# TriacFanout.net
KiCad netlist of a schematic drawn in EAGLE
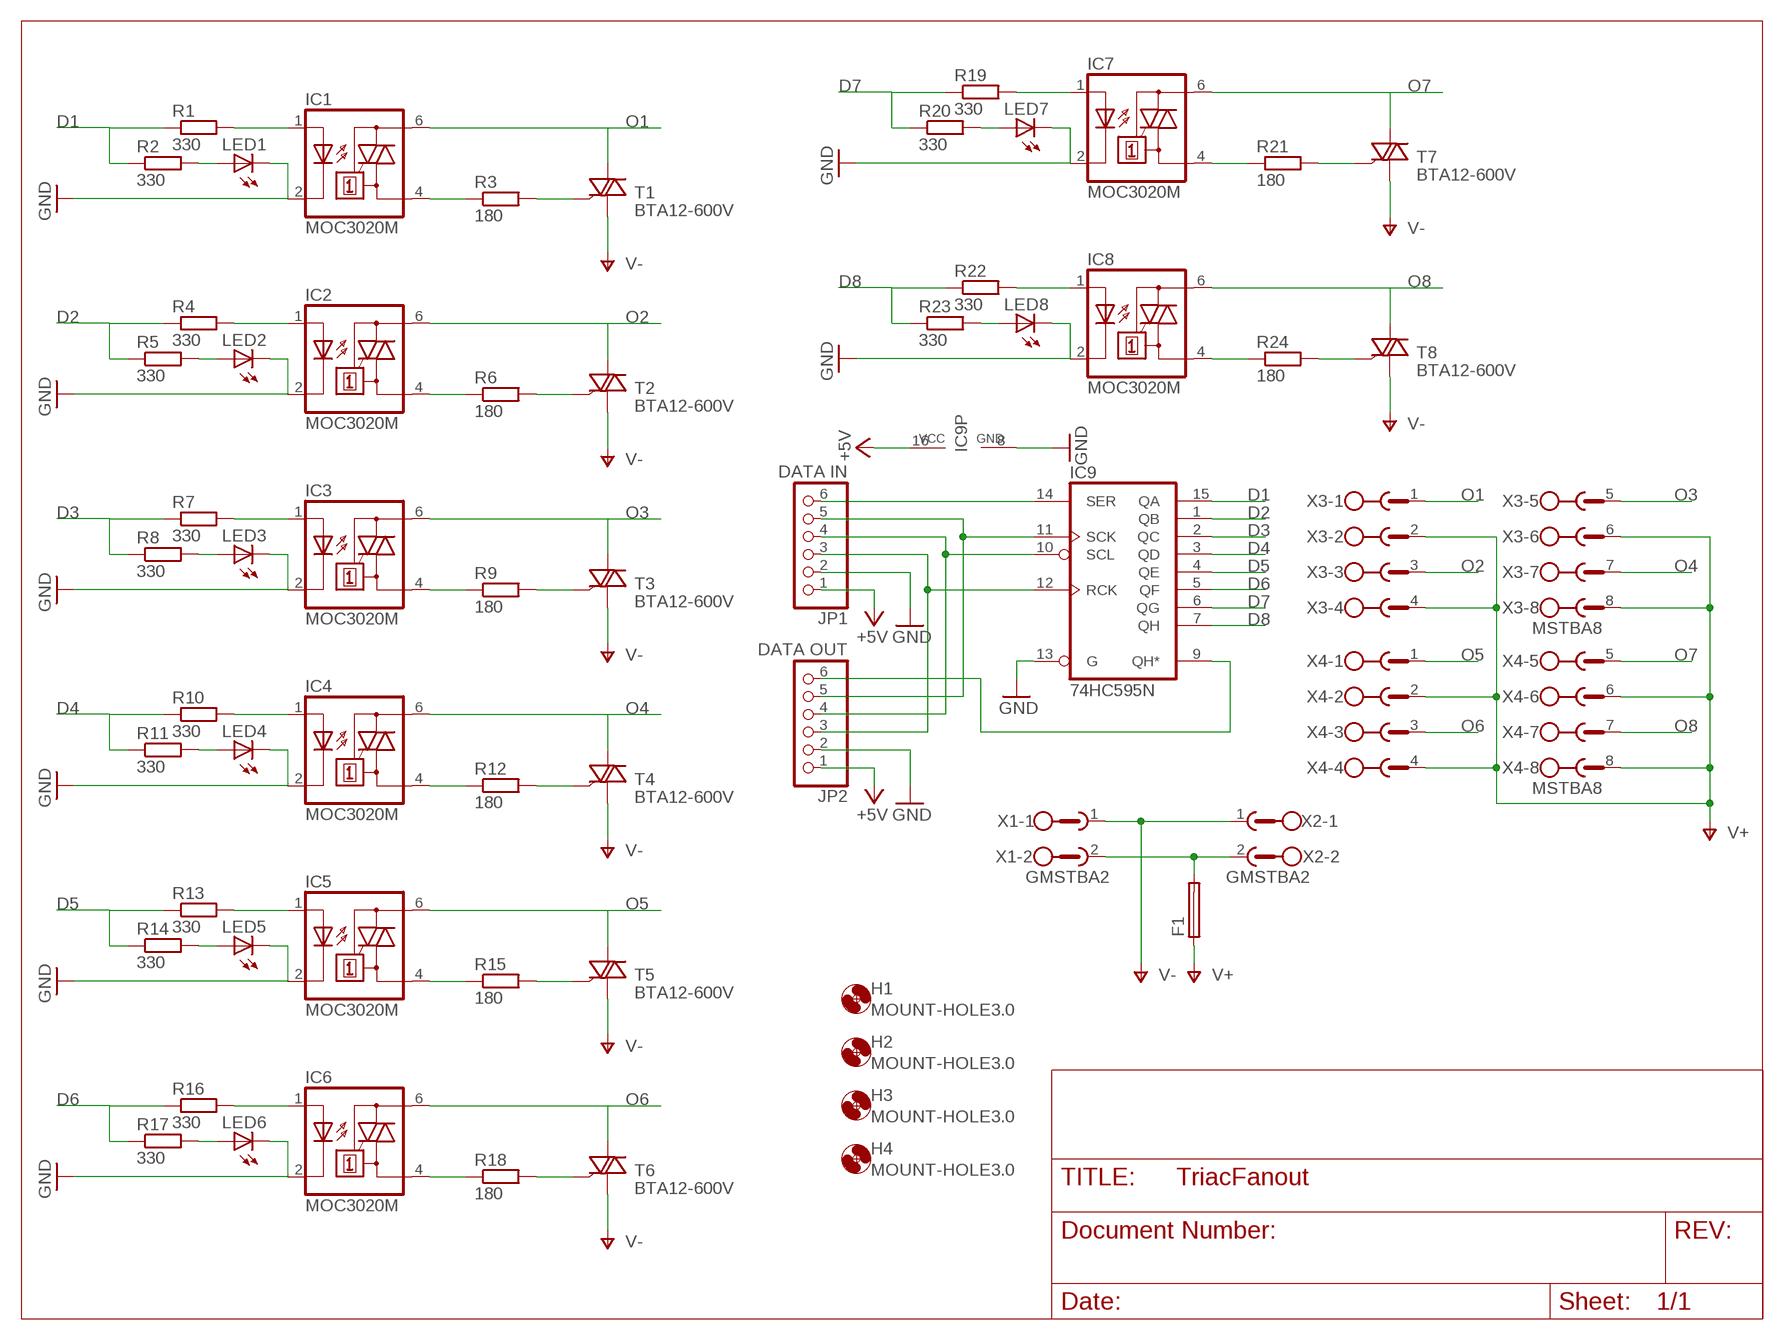
[diagram p0: schematic, sheet 1]

(export (version "E")
  (design (tool "Eeschema 10.0.6"))
  (components
    (comp (ref "F1")
      (value "SH22,5")
      (footprint "eagle-import:SH22,5")
      (fields (field (name "MF") "SCHURTER") (field (name "MPN") "0031.8201"))
      (libsource (lib "eagle-import") (part "SH22,5"))
    )
    (comp (ref "H1")
      (value "MOUNT-HOLE3.0")
      (footprint "eagle-import:3,0")
      (libsource (lib "eagle-import") (part "MOUNT-HOLE3.0"))
    )
    (comp (ref "H2")
      (value "MOUNT-HOLE3.0")
      (footprint "eagle-import:3,0")
      (libsource (lib "eagle-import") (part "MOUNT-HOLE3.0"))
    )
    (comp (ref "H3")
      (value "MOUNT-HOLE3.0")
      (footprint "eagle-import:3,0")
      (libsource (lib "eagle-import") (part "MOUNT-HOLE3.0"))
    )
    (comp (ref "H4")
      (value "MOUNT-HOLE3.0")
      (footprint "eagle-import:3,0")
      (libsource (lib "eagle-import") (part "MOUNT-HOLE3.0"))
    )
    (comp (ref "IC1")
      (value "MOC3020M")
      (footprint "eagle-import:DIL06")
      (fields (field (name "MF") "FAIRCHILD SEMICONDUCTOR") (field (name "MPN") "MOC3020-M"))
      (libsource (lib "eagle-import") (part "MOC30M20"))
    )
    (comp (ref "IC2")
      (value "MOC3020M")
      (footprint "eagle-import:DIL06")
      (fields (field (name "MF") "FAIRCHILD SEMICONDUCTOR") (field (name "MPN") "MOC3020-M"))
      (libsource (lib "eagle-import") (part "MOC30M20"))
    )
    (comp (ref "IC3")
      (value "MOC3020M")
      (footprint "eagle-import:DIL06")
      (fields (field (name "MF") "FAIRCHILD SEMICONDUCTOR") (field (name "MPN") "MOC3020-M"))
      (libsource (lib "eagle-import") (part "MOC30M20"))
    )
    (comp (ref "IC4")
      (value "MOC3020M")
      (footprint "eagle-import:DIL06")
      (fields (field (name "MF") "FAIRCHILD SEMICONDUCTOR") (field (name "MPN") "MOC3020-M"))
      (libsource (lib "eagle-import") (part "MOC30M20"))
    )
    (comp (ref "IC5")
      (value "MOC3020M")
      (footprint "eagle-import:DIL06")
      (fields (field (name "MF") "FAIRCHILD SEMICONDUCTOR") (field (name "MPN") "MOC3020-M"))
      (libsource (lib "eagle-import") (part "MOC30M20"))
    )
    (comp (ref "IC6")
      (value "MOC3020M")
      (footprint "eagle-import:DIL06")
      (fields (field (name "MF") "FAIRCHILD SEMICONDUCTOR") (field (name "MPN") "MOC3020-M"))
      (libsource (lib "eagle-import") (part "MOC30M20"))
    )
    (comp (ref "IC7")
      (value "MOC3020M")
      (footprint "eagle-import:DIL06")
      (fields (field (name "MF") "FAIRCHILD SEMICONDUCTOR") (field (name "MPN") "MOC3020-M"))
      (libsource (lib "eagle-import") (part "MOC30M20"))
    )
    (comp (ref "IC8")
      (value "MOC3020M")
      (footprint "eagle-import:DIL06")
      (fields (field (name "MF") "FAIRCHILD SEMICONDUCTOR") (field (name "MPN") "MOC3020-M"))
      (libsource (lib "eagle-import") (part "MOC30M20"))
    )
    (comp (ref "IC9")
      (value "74HC595N")
      (footprint "eagle-import:DIL16")
      (libsource (lib "eagle-import") (part "74595NHC"))
    )
    (comp (ref "JP1")
      (value "DATA IN")
      (footprint "eagle-import:1X06")
      (libsource (lib "eagle-import") (part "PINHD-1X6"))
    )
    (comp (ref "JP2")
      (value "DATA OUT")
      (footprint "eagle-import:1X06")
      (libsource (lib "eagle-import") (part "PINHD-1X6"))
    )
    (comp (ref "LED1")
      (value "LED5MM")
      (footprint "eagle-import:LED5MM")
      (libsource (lib "eagle-import") (part "LED5MM"))
    )
    (comp (ref "LED2")
      (value "LED5MM")
      (footprint "eagle-import:LED5MM")
      (libsource (lib "eagle-import") (part "LED5MM"))
    )
    (comp (ref "LED3")
      (value "LED5MM")
      (footprint "eagle-import:LED5MM")
      (libsource (lib "eagle-import") (part "LED5MM"))
    )
    (comp (ref "LED4")
      (value "LED5MM")
      (footprint "eagle-import:LED5MM")
      (libsource (lib "eagle-import") (part "LED5MM"))
    )
    (comp (ref "LED5")
      (value "LED5MM")
      (footprint "eagle-import:LED5MM")
      (libsource (lib "eagle-import") (part "LED5MM"))
    )
    (comp (ref "LED6")
      (value "LED5MM")
      (footprint "eagle-import:LED5MM")
      (libsource (lib "eagle-import") (part "LED5MM"))
    )
    (comp (ref "LED7")
      (value "LED5MM")
      (footprint "eagle-import:LED5MM")
      (libsource (lib "eagle-import") (part "LED5MM"))
    )
    (comp (ref "LED8")
      (value "LED5MM")
      (footprint "eagle-import:LED5MM")
      (libsource (lib "eagle-import") (part "LED5MM"))
    )
    (comp (ref "R1")
      (value "330")
      (footprint "eagle-import:0204_7")
      (libsource (lib "eagle-import") (part "R-EU_0204/7"))
    )
    (comp (ref "R2")
      (value "330")
      (footprint "eagle-import:0204_7")
      (libsource (lib "eagle-import") (part "R-EU_0204/7"))
    )
    (comp (ref "R3")
      (value "180")
      (footprint "eagle-import:0204_7")
      (libsource (lib "eagle-import") (part "R-EU_0204/7"))
    )
    (comp (ref "R4")
      (value "330")
      (footprint "eagle-import:0204_7")
      (libsource (lib "eagle-import") (part "R-EU_0204/7"))
    )
    (comp (ref "R5")
      (value "330")
      (footprint "eagle-import:0204_7")
      (libsource (lib "eagle-import") (part "R-EU_0204/7"))
    )
    (comp (ref "R6")
      (value "180")
      (footprint "eagle-import:0204_7")
      (libsource (lib "eagle-import") (part "R-EU_0204/7"))
    )
    (comp (ref "R7")
      (value "330")
      (footprint "eagle-import:0204_7")
      (libsource (lib "eagle-import") (part "R-EU_0204/7"))
    )
    (comp (ref "R8")
      (value "330")
      (footprint "eagle-import:0204_7")
      (libsource (lib "eagle-import") (part "R-EU_0204/7"))
    )
    (comp (ref "R9")
      (value "180")
      (footprint "eagle-import:0204_7")
      (libsource (lib "eagle-import") (part "R-EU_0204/7"))
    )
    (comp (ref "R10")
      (value "330")
      (footprint "eagle-import:0204_7")
      (libsource (lib "eagle-import") (part "R-EU_0204/7"))
    )
    (comp (ref "R11")
      (value "330")
      (footprint "eagle-import:0204_7")
      (libsource (lib "eagle-import") (part "R-EU_0204/7"))
    )
    (comp (ref "R12")
      (value "180")
      (footprint "eagle-import:0204_7")
      (libsource (lib "eagle-import") (part "R-EU_0204/7"))
    )
    (comp (ref "R13")
      (value "330")
      (footprint "eagle-import:0204_7")
      (libsource (lib "eagle-import") (part "R-EU_0204/7"))
    )
    (comp (ref "R14")
      (value "330")
      (footprint "eagle-import:0204_7")
      (libsource (lib "eagle-import") (part "R-EU_0204/7"))
    )
    (comp (ref "R15")
      (value "180")
      (footprint "eagle-import:0204_7")
      (libsource (lib "eagle-import") (part "R-EU_0204/7"))
    )
    (comp (ref "R16")
      (value "330")
      (footprint "eagle-import:0204_7")
      (libsource (lib "eagle-import") (part "R-EU_0204/7"))
    )
    (comp (ref "R17")
      (value "330")
      (footprint "eagle-import:0204_7")
      (libsource (lib "eagle-import") (part "R-EU_0204/7"))
    )
    (comp (ref "R18")
      (value "180")
      (footprint "eagle-import:0204_7")
      (libsource (lib "eagle-import") (part "R-EU_0204/7"))
    )
    (comp (ref "R19")
      (value "330")
      (footprint "eagle-import:0204_7")
      (libsource (lib "eagle-import") (part "R-EU_0204/7"))
    )
    (comp (ref "R20")
      (value "330")
      (footprint "eagle-import:0204_7")
      (libsource (lib "eagle-import") (part "R-EU_0204/7"))
    )
    (comp (ref "R21")
      (value "180")
      (footprint "eagle-import:0204_7")
      (libsource (lib "eagle-import") (part "R-EU_0204/7"))
    )
    (comp (ref "R22")
      (value "330")
      (footprint "eagle-import:0204_7")
      (libsource (lib "eagle-import") (part "R-EU_0204/7"))
    )
    (comp (ref "R23")
      (value "330")
      (footprint "eagle-import:0204_7")
      (libsource (lib "eagle-import") (part "R-EU_0204/7"))
    )
    (comp (ref "R24")
      (value "180")
      (footprint "eagle-import:0204_7")
      (libsource (lib "eagle-import") (part "R-EU_0204/7"))
    )
    (comp (ref "T1")
      (value "BTA12-600V")
      (footprint "eagle-import:TO220V")
      (libsource (lib "eagle-import") (part "BTA12-600V"))
    )
    (comp (ref "T2")
      (value "BTA12-600V")
      (footprint "eagle-import:TO220V")
      (libsource (lib "eagle-import") (part "BTA12-600V"))
    )
    (comp (ref "T3")
      (value "BTA12-600V")
      (footprint "eagle-import:TO220V")
      (libsource (lib "eagle-import") (part "BTA12-600V"))
    )
    (comp (ref "T4")
      (value "BTA12-600V")
      (footprint "eagle-import:TO220V")
      (libsource (lib "eagle-import") (part "BTA12-600V"))
    )
    (comp (ref "T5")
      (value "BTA12-600V")
      (footprint "eagle-import:TO220V")
      (libsource (lib "eagle-import") (part "BTA12-600V"))
    )
    (comp (ref "T6")
      (value "BTA12-600V")
      (footprint "eagle-import:TO220V")
      (libsource (lib "eagle-import") (part "BTA12-600V"))
    )
    (comp (ref "T7")
      (value "BTA12-600V")
      (footprint "eagle-import:TO220V")
      (libsource (lib "eagle-import") (part "BTA12-600V"))
    )
    (comp (ref "T8")
      (value "BTA12-600V")
      (footprint "eagle-import:TO220V")
      (libsource (lib "eagle-import") (part "BTA12-600V"))
    )
    (comp (ref "X1")
      (value "GMSTBA2")
      (footprint "eagle-import:GMSTBA2")
      (fields (field (name "MF") "FARNELL") (field (name "MPN") "1757242"))
      (libsource (lib "eagle-import") (part "GMSTBA2"))
    )
    (comp (ref "X2")
      (value "GMSTBA2")
      (footprint "eagle-import:GMSTBA2")
      (fields (field (name "MF") "FARNELL") (field (name "MPN") "1757242"))
      (libsource (lib "eagle-import") (part "GMSTBA2"))
    )
    (comp (ref "X3")
      (value "MSTBA8")
      (footprint "eagle-import:MSTBA8")
      (fields (field (name "MF") "FARNELL") (field (name "MPN") "1757307"))
      (libsource (lib "eagle-import") (part "MSTBA8"))
    )
    (comp (ref "X4")
      (value "MSTBA8")
      (footprint "eagle-import:MSTBA8")
      (fields (field (name "MF") "FARNELL") (field (name "MPN") "1757307"))
      (libsource (lib "eagle-import") (part "MSTBA8"))
    )
  )
  (nets
    (net (code "1") (name "+5V") (class "Default")
      (node (ref "IC9") (pin "16") (pinfunction "VCC_16") (pintype "power_in"))
      (node (ref "JP1") (pin "1") (pinfunction "1_1") (pintype "passive"))
      (node (ref "JP2") (pin "1") (pinfunction "1_1") (pintype "passive"))
    )
    (net (code "2") (name "/D1") (class "Default")
      (node (ref "IC9") (pin "15") (pinfunction "QA_15") (pintype "tri_state"))
      (node (ref "R1") (pin "1") (pinfunction "1_1") (pintype "passive"))
      (node (ref "R2") (pin "1") (pinfunction "1_1") (pintype "passive"))
    )
    (net (code "3") (name "/D2") (class "Default")
      (node (ref "IC9") (pin "1") (pinfunction "QB_1") (pintype "tri_state"))
      (node (ref "R4") (pin "1") (pinfunction "1_1") (pintype "passive"))
      (node (ref "R5") (pin "1") (pinfunction "1_1") (pintype "passive"))
    )
    (net (code "4") (name "/D3") (class "Default")
      (node (ref "IC9") (pin "2") (pinfunction "QC_2") (pintype "tri_state"))
      (node (ref "R7") (pin "1") (pinfunction "1_1") (pintype "passive"))
      (node (ref "R8") (pin "1") (pinfunction "1_1") (pintype "passive"))
    )
    (net (code "5") (name "/D4") (class "Default")
      (node (ref "IC9") (pin "3") (pinfunction "QD_3") (pintype "tri_state"))
      (node (ref "R10") (pin "1") (pinfunction "1_1") (pintype "passive"))
      (node (ref "R11") (pin "1") (pinfunction "1_1") (pintype "passive"))
    )
    (net (code "6") (name "/D5") (class "Default")
      (node (ref "IC9") (pin "4") (pinfunction "QE_4") (pintype "tri_state"))
      (node (ref "R13") (pin "1") (pinfunction "1_1") (pintype "passive"))
      (node (ref "R14") (pin "1") (pinfunction "1_1") (pintype "passive"))
    )
    (net (code "7") (name "/D6") (class "Default")
      (node (ref "IC9") (pin "5") (pinfunction "QF_5") (pintype "tri_state"))
      (node (ref "R16") (pin "1") (pinfunction "1_1") (pintype "passive"))
      (node (ref "R17") (pin "1") (pinfunction "1_1") (pintype "passive"))
    )
    (net (code "8") (name "/D7") (class "Default")
      (node (ref "IC9") (pin "6") (pinfunction "QG_6") (pintype "tri_state"))
      (node (ref "R19") (pin "1") (pinfunction "1_1") (pintype "passive"))
      (node (ref "R20") (pin "1") (pinfunction "1_1") (pintype "passive"))
    )
    (net (code "9") (name "/D8") (class "Default")
      (node (ref "IC9") (pin "7") (pinfunction "QH_7") (pintype "tri_state"))
      (node (ref "R22") (pin "1") (pinfunction "1_1") (pintype "passive"))
      (node (ref "R23") (pin "1") (pinfunction "1_1") (pintype "passive"))
    )
    (net (code "10") (name "/O1") (class "Default")
      (node (ref "IC1") (pin "6") (pinfunction "A2_6") (pintype "passive"))
      (node (ref "T1") (pin "2") (pinfunction "A2_2") (pintype "passive"))
      (node (ref "X3") (pin "1") (pinfunction "1_1") (pintype "passive"))
    )
    (net (code "11") (name "/O2") (class "Default")
      (node (ref "IC2") (pin "6") (pinfunction "A2_6") (pintype "passive"))
      (node (ref "T2") (pin "2") (pinfunction "A2_2") (pintype "passive"))
      (node (ref "X3") (pin "3") (pinfunction "1_3") (pintype "passive"))
    )
    (net (code "12") (name "/O3") (class "Default")
      (node (ref "IC3") (pin "6") (pinfunction "A2_6") (pintype "passive"))
      (node (ref "T3") (pin "2") (pinfunction "A2_2") (pintype "passive"))
      (node (ref "X3") (pin "5") (pinfunction "1_5") (pintype "passive"))
    )
    (net (code "13") (name "/O4") (class "Default")
      (node (ref "IC4") (pin "6") (pinfunction "A2_6") (pintype "passive"))
      (node (ref "T4") (pin "2") (pinfunction "A2_2") (pintype "passive"))
      (node (ref "X3") (pin "7") (pinfunction "1_7") (pintype "passive"))
    )
    (net (code "14") (name "/O5") (class "Default")
      (node (ref "IC5") (pin "6") (pinfunction "A2_6") (pintype "passive"))
      (node (ref "T5") (pin "2") (pinfunction "A2_2") (pintype "passive"))
      (node (ref "X4") (pin "1") (pinfunction "1_1") (pintype "passive"))
    )
    (net (code "15") (name "/O6") (class "Default")
      (node (ref "IC6") (pin "6") (pinfunction "A2_6") (pintype "passive"))
      (node (ref "T6") (pin "2") (pinfunction "A2_2") (pintype "passive"))
      (node (ref "X4") (pin "3") (pinfunction "1_3") (pintype "passive"))
    )
    (net (code "16") (name "/O7") (class "Default")
      (node (ref "IC7") (pin "6") (pinfunction "A2_6") (pintype "passive"))
      (node (ref "T7") (pin "2") (pinfunction "A2_2") (pintype "passive"))
      (node (ref "X4") (pin "5") (pinfunction "1_5") (pintype "passive"))
    )
    (net (code "17") (name "/O8") (class "Default")
      (node (ref "IC8") (pin "6") (pinfunction "A2_6") (pintype "passive"))
      (node (ref "T8") (pin "2") (pinfunction "A2_2") (pintype "passive"))
      (node (ref "X4") (pin "7") (pinfunction "1_7") (pintype "passive"))
    )
    (net (code "18") (name "GND") (class "Default")
      (node (ref "IC1") (pin "2") (pinfunction "C_2") (pintype "passive"))
      (node (ref "IC2") (pin "2") (pinfunction "C_2") (pintype "passive"))
      (node (ref "IC3") (pin "2") (pinfunction "C_2") (pintype "passive"))
      (node (ref "IC4") (pin "2") (pinfunction "C_2") (pintype "passive"))
      (node (ref "IC5") (pin "2") (pinfunction "C_2") (pintype "passive"))
      (node (ref "IC6") (pin "2") (pinfunction "C_2") (pintype "passive"))
      (node (ref "IC7") (pin "2") (pinfunction "C_2") (pintype "passive"))
      (node (ref "IC8") (pin "2") (pinfunction "C_2") (pintype "passive"))
      (node (ref "IC9") (pin "13") (pinfunction "G_13") (pintype "input"))
      (node (ref "IC9") (pin "8") (pinfunction "GND_8") (pintype "power_in"))
      (node (ref "JP1") (pin "2") (pinfunction "2_2") (pintype "passive"))
      (node (ref "JP2") (pin "2") (pinfunction "2_2") (pintype "passive"))
      (node (ref "LED1") (pin "K") (pinfunction "C_K") (pintype "passive"))
      (node (ref "LED2") (pin "K") (pinfunction "C_K") (pintype "passive"))
      (node (ref "LED3") (pin "K") (pinfunction "C_K") (pintype "passive"))
      (node (ref "LED4") (pin "K") (pinfunction "C_K") (pintype "passive"))
      (node (ref "LED5") (pin "K") (pinfunction "C_K") (pintype "passive"))
      (node (ref "LED6") (pin "K") (pinfunction "C_K") (pintype "passive"))
      (node (ref "LED7") (pin "K") (pinfunction "C_K") (pintype "passive"))
      (node (ref "LED8") (pin "K") (pinfunction "C_K") (pintype "passive"))
    )
    (net (code "19") (name "Net-(IC1-A)") (class "Default")
      (node (ref "IC1") (pin "1") (pinfunction "A_1") (pintype "passive"))
      (node (ref "R1") (pin "2") (pinfunction "2_2") (pintype "passive"))
    )
    (net (code "20") (name "Net-(IC1-A1)") (class "Default")
      (node (ref "IC1") (pin "4") (pinfunction "A1_4") (pintype "passive"))
      (node (ref "R3") (pin "1") (pinfunction "1_1") (pintype "passive"))
    )
    (net (code "21") (name "Net-(IC2-A)") (class "Default")
      (node (ref "IC2") (pin "1") (pinfunction "A_1") (pintype "passive"))
      (node (ref "R4") (pin "2") (pinfunction "2_2") (pintype "passive"))
    )
    (net (code "22") (name "Net-(IC2-A1)") (class "Default")
      (node (ref "IC2") (pin "4") (pinfunction "A1_4") (pintype "passive"))
      (node (ref "R6") (pin "1") (pinfunction "1_1") (pintype "passive"))
    )
    (net (code "23") (name "Net-(IC3-A)") (class "Default")
      (node (ref "IC3") (pin "1") (pinfunction "A_1") (pintype "passive"))
      (node (ref "R7") (pin "2") (pinfunction "2_2") (pintype "passive"))
    )
    (net (code "24") (name "Net-(IC3-A1)") (class "Default")
      (node (ref "IC3") (pin "4") (pinfunction "A1_4") (pintype "passive"))
      (node (ref "R9") (pin "1") (pinfunction "1_1") (pintype "passive"))
    )
    (net (code "25") (name "Net-(IC4-A)") (class "Default")
      (node (ref "IC4") (pin "1") (pinfunction "A_1") (pintype "passive"))
      (node (ref "R10") (pin "2") (pinfunction "2_2") (pintype "passive"))
    )
    (net (code "26") (name "Net-(IC4-A1)") (class "Default")
      (node (ref "IC4") (pin "4") (pinfunction "A1_4") (pintype "passive"))
      (node (ref "R12") (pin "1") (pinfunction "1_1") (pintype "passive"))
    )
    (net (code "27") (name "Net-(IC5-A)") (class "Default")
      (node (ref "IC5") (pin "1") (pinfunction "A_1") (pintype "passive"))
      (node (ref "R13") (pin "2") (pinfunction "2_2") (pintype "passive"))
    )
    (net (code "28") (name "Net-(IC5-A1)") (class "Default")
      (node (ref "IC5") (pin "4") (pinfunction "A1_4") (pintype "passive"))
      (node (ref "R15") (pin "1") (pinfunction "1_1") (pintype "passive"))
    )
    (net (code "29") (name "Net-(IC6-A)") (class "Default")
      (node (ref "IC6") (pin "1") (pinfunction "A_1") (pintype "passive"))
      (node (ref "R16") (pin "2") (pinfunction "2_2") (pintype "passive"))
    )
    (net (code "30") (name "Net-(IC6-A1)") (class "Default")
      (node (ref "IC6") (pin "4") (pinfunction "A1_4") (pintype "passive"))
      (node (ref "R18") (pin "1") (pinfunction "1_1") (pintype "passive"))
    )
    (net (code "31") (name "Net-(IC7-A)") (class "Default")
      (node (ref "IC7") (pin "1") (pinfunction "A_1") (pintype "passive"))
      (node (ref "R19") (pin "2") (pinfunction "2_2") (pintype "passive"))
    )
    (net (code "32") (name "Net-(IC7-A1)") (class "Default")
      (node (ref "IC7") (pin "4") (pinfunction "A1_4") (pintype "passive"))
      (node (ref "R21") (pin "1") (pinfunction "1_1") (pintype "passive"))
    )
    (net (code "33") (name "Net-(IC8-A)") (class "Default")
      (node (ref "IC8") (pin "1") (pinfunction "A_1") (pintype "passive"))
      (node (ref "R22") (pin "2") (pinfunction "2_2") (pintype "passive"))
    )
    (net (code "34") (name "Net-(IC8-A1)") (class "Default")
      (node (ref "IC8") (pin "4") (pinfunction "A1_4") (pintype "passive"))
      (node (ref "R24") (pin "1") (pinfunction "1_1") (pintype "passive"))
    )
    (net (code "35") (name "Net-(IC9A-QH*)") (class "Default")
      (node (ref "IC9") (pin "9") (pinfunction "QH*_9") (pintype "tri_state"))
      (node (ref "JP2") (pin "6") (pinfunction "6_6") (pintype "passive"))
    )
    (net (code "36") (name "Net-(IC9A-RCK)") (class "Default")
      (node (ref "IC9") (pin "12") (pinfunction "RCK_12") (pintype "input"))
      (node (ref "JP1") (pin "3") (pinfunction "3_3") (pintype "passive"))
      (node (ref "JP2") (pin "3") (pinfunction "3_3") (pintype "passive"))
    )
    (net (code "37") (name "Net-(IC9A-SCK)") (class "Default")
      (node (ref "IC9") (pin "11") (pinfunction "SCK_11") (pintype "input"))
      (node (ref "JP1") (pin "5") (pinfunction "5_5") (pintype "passive"))
      (node (ref "JP2") (pin "5") (pinfunction "5_5") (pintype "passive"))
    )
    (net (code "38") (name "Net-(IC9A-SCL)") (class "Default")
      (node (ref "IC9") (pin "10") (pinfunction "SCL_10") (pintype "input"))
      (node (ref "JP1") (pin "4") (pinfunction "4_4") (pintype "passive"))
      (node (ref "JP2") (pin "4") (pinfunction "4_4") (pintype "passive"))
    )
    (net (code "39") (name "Net-(IC9A-SER)") (class "Default")
      (node (ref "IC9") (pin "14") (pinfunction "SER_14") (pintype "input"))
      (node (ref "JP1") (pin "6") (pinfunction "6_6") (pintype "passive"))
    )
    (net (code "40") (name "Net-(LED1-PadA)") (class "Default")
      (node (ref "LED1") (pin "A") (pinfunction "A_A") (pintype "passive"))
      (node (ref "R2") (pin "2") (pinfunction "2_2") (pintype "passive"))
    )
    (net (code "41") (name "Net-(LED2-PadA)") (class "Default")
      (node (ref "LED2") (pin "A") (pinfunction "A_A") (pintype "passive"))
      (node (ref "R5") (pin "2") (pinfunction "2_2") (pintype "passive"))
    )
    (net (code "42") (name "Net-(LED3-PadA)") (class "Default")
      (node (ref "LED3") (pin "A") (pinfunction "A_A") (pintype "passive"))
      (node (ref "R8") (pin "2") (pinfunction "2_2") (pintype "passive"))
    )
    (net (code "43") (name "Net-(LED4-PadA)") (class "Default")
      (node (ref "LED4") (pin "A") (pinfunction "A_A") (pintype "passive"))
      (node (ref "R11") (pin "2") (pinfunction "2_2") (pintype "passive"))
    )
    (net (code "44") (name "Net-(LED5-PadA)") (class "Default")
      (node (ref "LED5") (pin "A") (pinfunction "A_A") (pintype "passive"))
      (node (ref "R14") (pin "2") (pinfunction "2_2") (pintype "passive"))
    )
    (net (code "45") (name "Net-(LED6-PadA)") (class "Default")
      (node (ref "LED6") (pin "A") (pinfunction "A_A") (pintype "passive"))
      (node (ref "R17") (pin "2") (pinfunction "2_2") (pintype "passive"))
    )
    (net (code "46") (name "Net-(LED7-PadA)") (class "Default")
      (node (ref "LED7") (pin "A") (pinfunction "A_A") (pintype "passive"))
      (node (ref "R20") (pin "2") (pinfunction "2_2") (pintype "passive"))
    )
    (net (code "47") (name "Net-(LED8-PadA)") (class "Default")
      (node (ref "LED8") (pin "A") (pinfunction "A_A") (pintype "passive"))
      (node (ref "R23") (pin "2") (pinfunction "2_2") (pintype "passive"))
    )
    (net (code "48") (name "Net-(T1-G)") (class "Default")
      (node (ref "R3") (pin "2") (pinfunction "2_2") (pintype "passive"))
      (node (ref "T1") (pin "3") (pinfunction "G_3") (pintype "passive"))
    )
    (net (code "49") (name "Net-(T2-G)") (class "Default")
      (node (ref "R6") (pin "2") (pinfunction "2_2") (pintype "passive"))
      (node (ref "T2") (pin "3") (pinfunction "G_3") (pintype "passive"))
    )
    (net (code "50") (name "Net-(T3-G)") (class "Default")
      (node (ref "R9") (pin "2") (pinfunction "2_2") (pintype "passive"))
      (node (ref "T3") (pin "3") (pinfunction "G_3") (pintype "passive"))
    )
    (net (code "51") (name "Net-(T4-G)") (class "Default")
      (node (ref "R12") (pin "2") (pinfunction "2_2") (pintype "passive"))
      (node (ref "T4") (pin "3") (pinfunction "G_3") (pintype "passive"))
    )
    (net (code "52") (name "Net-(T5-G)") (class "Default")
      (node (ref "R15") (pin "2") (pinfunction "2_2") (pintype "passive"))
      (node (ref "T5") (pin "3") (pinfunction "G_3") (pintype "passive"))
    )
    (net (code "53") (name "Net-(T6-G)") (class "Default")
      (node (ref "R18") (pin "2") (pinfunction "2_2") (pintype "passive"))
      (node (ref "T6") (pin "3") (pinfunction "G_3") (pintype "passive"))
    )
    (net (code "54") (name "Net-(T7-G)") (class "Default")
      (node (ref "R21") (pin "2") (pinfunction "2_2") (pintype "passive"))
      (node (ref "T7") (pin "3") (pinfunction "G_3") (pintype "passive"))
    )
    (net (code "55") (name "Net-(T8-G)") (class "Default")
      (node (ref "R24") (pin "2") (pinfunction "2_2") (pintype "passive"))
      (node (ref "T8") (pin "3") (pinfunction "G_3") (pintype "passive"))
    )
    (net (code "56") (name "Net-(X1B-1)") (class "Default")
      (node (ref "F1") (pin "2") (pinfunction "2_2") (pintype "passive"))
      (node (ref "X1") (pin "2") (pinfunction "1_2") (pintype "passive"))
      (node (ref "X2") (pin "2") (pinfunction "1_2") (pintype "passive"))
    )
    (net (code "57") (name "V+") (class "Default")
      (node (ref "F1") (pin "1") (pinfunction "1_1") (pintype "passive"))
      (node (ref "X3") (pin "2") (pinfunction "1_2") (pintype "passive"))
      (node (ref "X3") (pin "4") (pinfunction "1_4") (pintype "passive"))
      (node (ref "X3") (pin "6") (pinfunction "1_6") (pintype "passive"))
      (node (ref "X3") (pin "8") (pinfunction "1_8") (pintype "passive"))
      (node (ref "X4") (pin "2") (pinfunction "1_2") (pintype "passive"))
      (node (ref "X4") (pin "4") (pinfunction "1_4") (pintype "passive"))
      (node (ref "X4") (pin "6") (pinfunction "1_6") (pintype "passive"))
      (node (ref "X4") (pin "8") (pinfunction "1_8") (pintype "passive"))
    )
    (net (code "58") (name "V-") (class "Default")
      (node (ref "T1") (pin "1") (pinfunction "A1_1") (pintype "passive"))
      (node (ref "T2") (pin "1") (pinfunction "A1_1") (pintype "passive"))
      (node (ref "T3") (pin "1") (pinfunction "A1_1") (pintype "passive"))
      (node (ref "T4") (pin "1") (pinfunction "A1_1") (pintype "passive"))
      (node (ref "T5") (pin "1") (pinfunction "A1_1") (pintype "passive"))
      (node (ref "T6") (pin "1") (pinfunction "A1_1") (pintype "passive"))
      (node (ref "T7") (pin "1") (pinfunction "A1_1") (pintype "passive"))
      (node (ref "T8") (pin "1") (pinfunction "A1_1") (pintype "passive"))
      (node (ref "X1") (pin "1") (pinfunction "1_1") (pintype "passive"))
      (node (ref "X2") (pin "1") (pinfunction "1_1") (pintype "passive"))
    )
  )
)
